# ControlMoteur_ESP32.net
KiCad netlist of a schematic drawn in EasyEDA
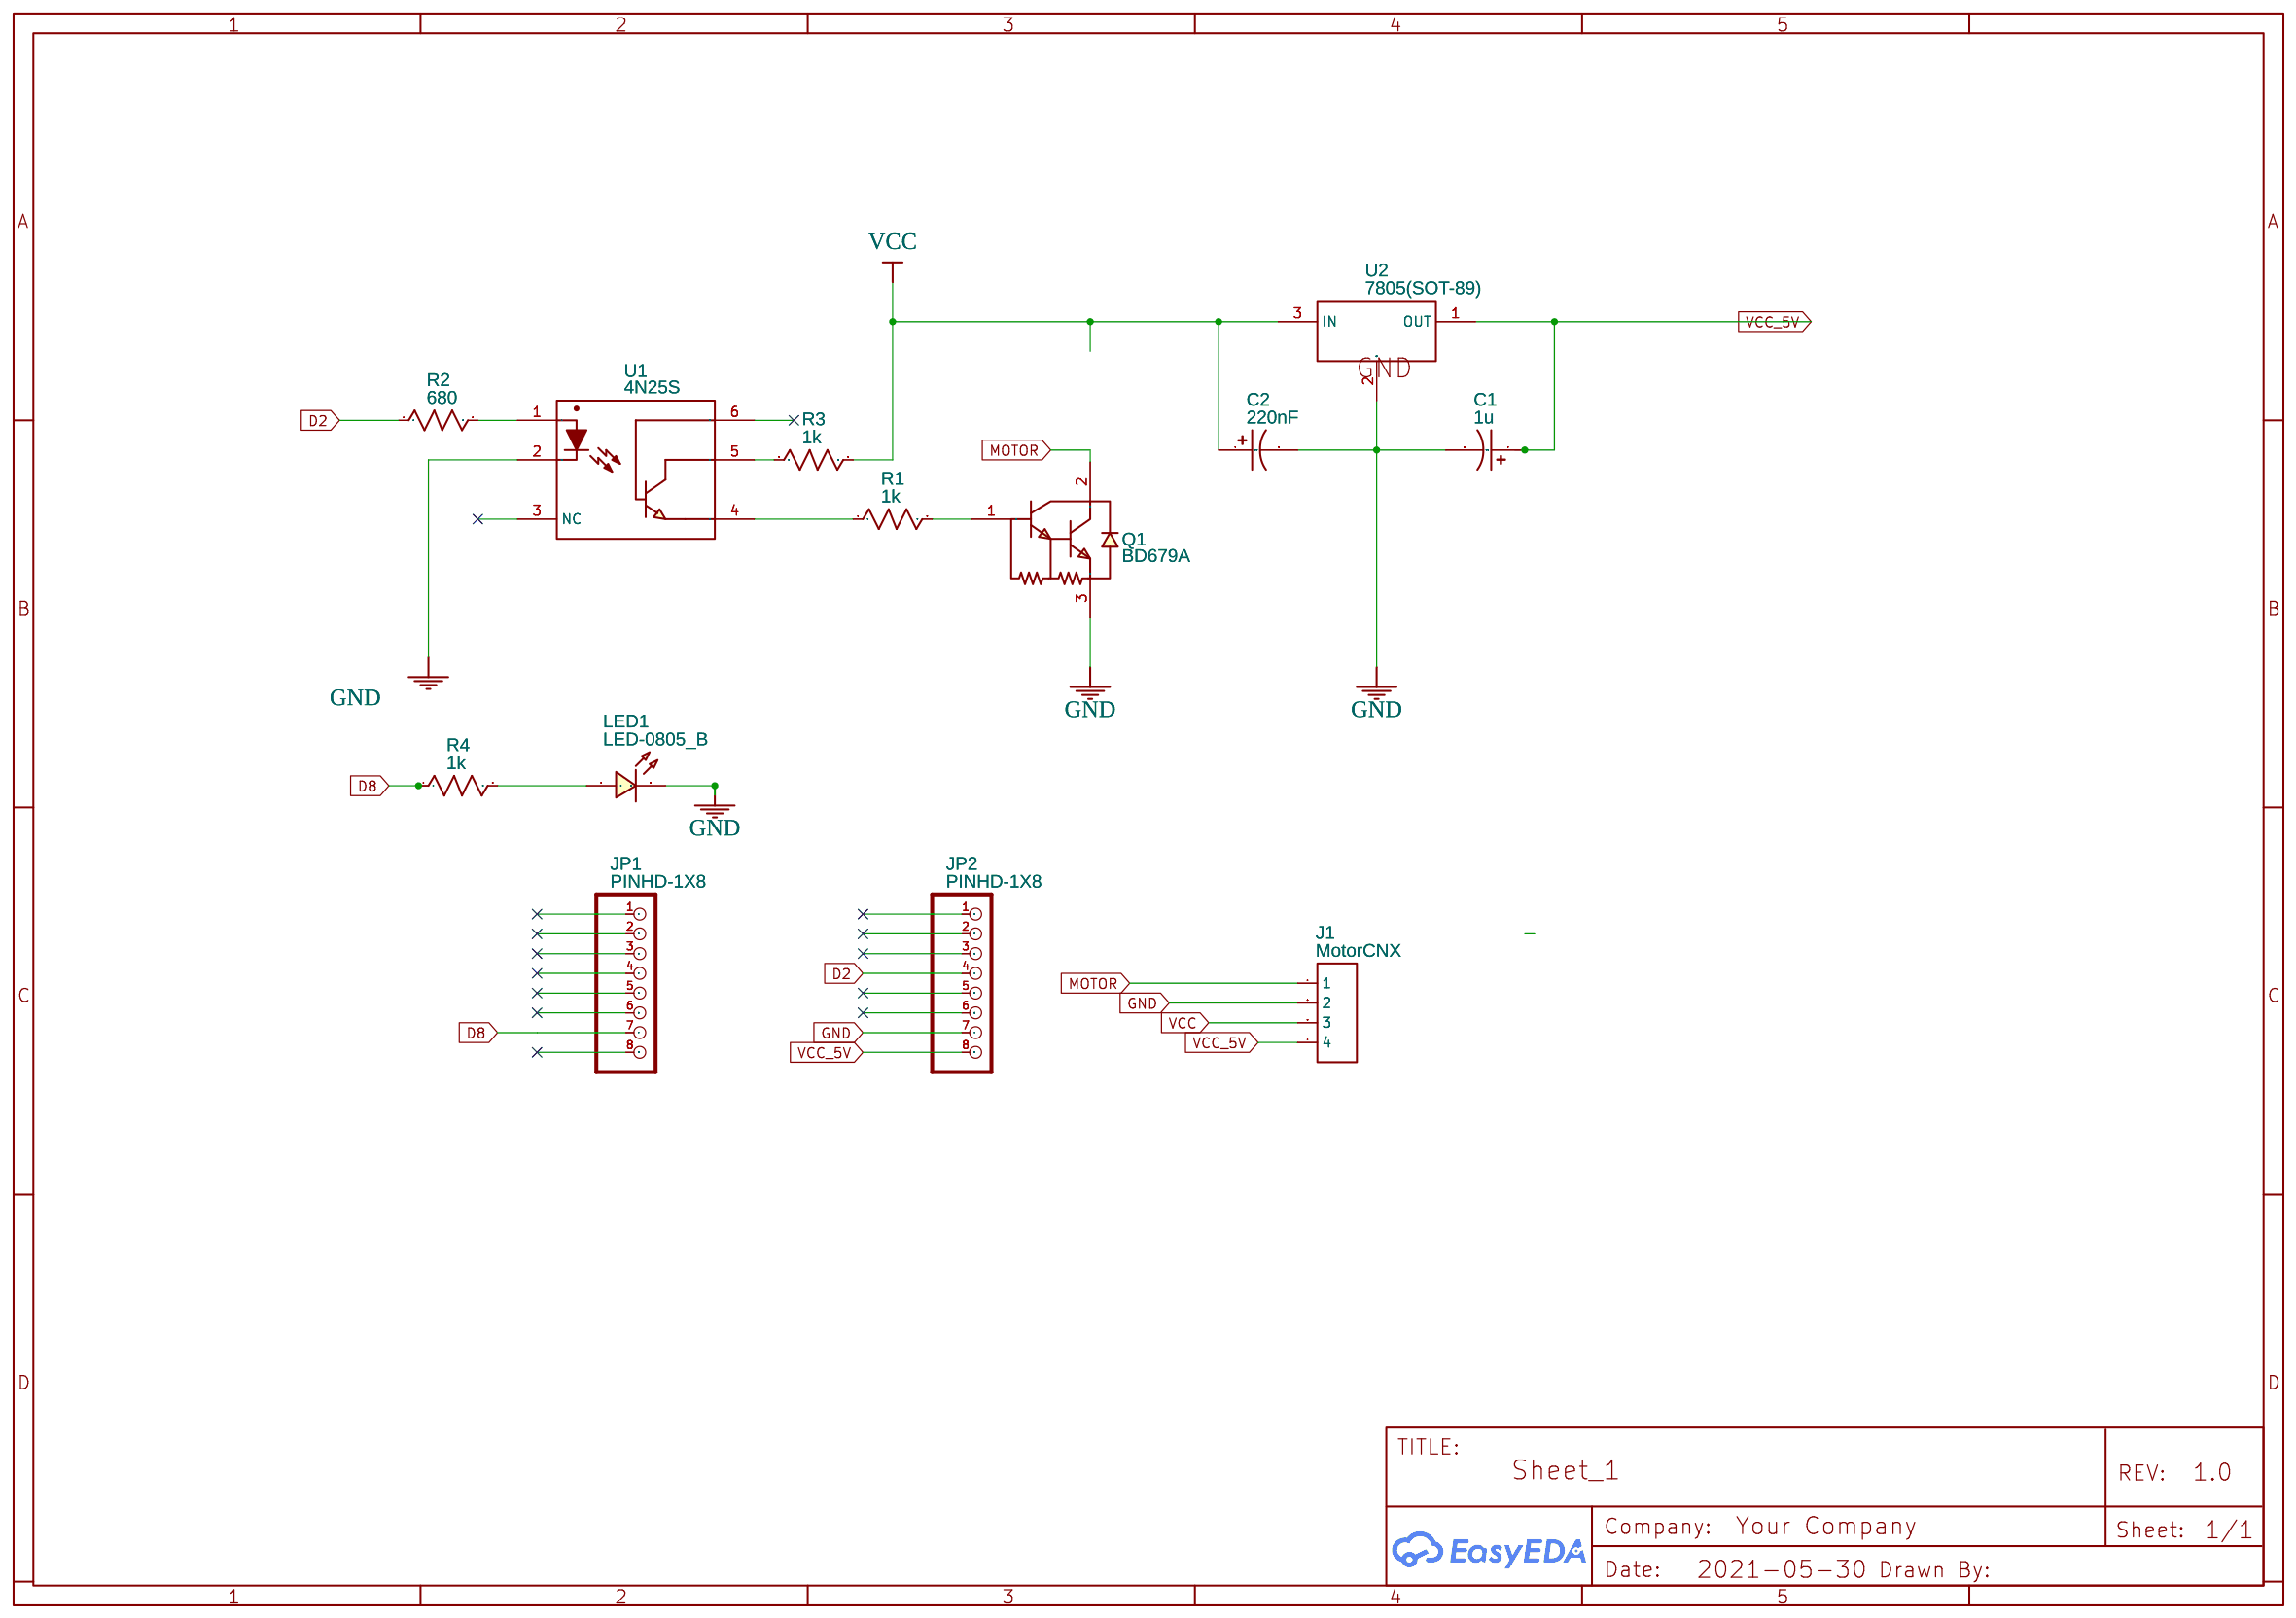
[diagram p0: schematic sheet]

(export (version "E")
  (design (tool "Eeschema 10.0.6"))
  (components
    (comp (ref "C1") (value "1u") (libsource (lib "") (part "C_Tan_SMD_A_US")))
    (comp (ref "C2") (value "220nF") (libsource (lib "") (part "C_Tan_SMD_A_US_1")))
    (comp (ref "J1")
      (value "MotorCNX")
      (fields (field (name "BOM_Supplier Part") "C124378"))
      (libsource (lib "") (part "HDR-M-2.54_1x4"))
    )
    (comp (ref "JP1")
      (value "PINHD-1X8")
      (fields (field (name "BOM_Supplier Part") "C492407"))
      (libsource (lib "") (part "PINHD-1X8"))
    )
    (comp (ref "JP2")
      (value "PINHD-1X8")
      (fields (field (name "BOM_Supplier Part") "C492407"))
      (libsource (lib "") (part "PINHD-1X8"))
    )
    (comp (ref "LED1")
      (value "LED-0805_B")
      (fields
        (field (name "BOM_Manufacturer Part") "D-B080508B1-KS2")
        (field (name "BOM_Supplier Part") "C108412")
      )
      (libsource (lib "") (part "LED-0805_B"))
    )
    (comp (ref "Q1")
      (value "BD679A")
      (fields (field (name "BOM_Supplier Part") "C2760771"))
      (libsource (lib "") (part "BD679A"))
    )
    (comp (ref "R1") (value "1k") (libsource (lib "") (part "R_1210_US")))
    (comp (ref "R2") (value "680") (libsource (lib "") (part "R_1210_US")))
    (comp (ref "R3") (value "1k") (libsource (lib "") (part "R_1210_US")))
    (comp (ref "R4") (value "1k") (libsource (lib "") (part "R_1210_US")))
    (comp (ref "U1")
      (value "4N25S")
      (fields (field (name "BOM_Supplier Part") "C143074"))
      (libsource (lib "") (part "4N25S"))
    )
    (comp (ref "U2")
      (value "7805(SOT-89)")
      (fields (field (name "BOM_Manufacturer Part") "CJ78L05") (field (name "BOM_Supplier Part") "C2079"))
      (libsource (lib "") (part "7805(SOT-89)"))
    )
  )
  (nets
    (net (code "1") (name "D2") (class "Default")
      (node (ref "JP2") (pin "4") (pinfunction "4_4") (pintype "unspecified"))
      (node (ref "R2") (pin "1") (pinfunction "1_1") (pintype "unspecified"))
    )
    (net (code "2") (name "D8") (class "Default")
      (node (ref "JP1") (pin "7") (pinfunction "7_7") (pintype "unspecified"))
      (node (ref "R4") (pin "1") (pinfunction "1_1") (pintype "unspecified"))
    )
    (net (code "3") (name "GND") (class "Default")
      (node (ref "C1") (pin "2") (pinfunction "2_2") (pintype "unspecified"))
      (node (ref "C2") (pin "2") (pinfunction "2_2") (pintype "unspecified"))
      (node (ref "J1") (pin "2") (pinfunction "2_2") (pintype "unspecified"))
      (node (ref "JP2") (pin "7") (pinfunction "7_7") (pintype "unspecified"))
      (node (ref "LED1") (pin "2") (pinfunction "2_2") (pintype "unspecified"))
      (node (ref "Q1") (pin "3") (pinfunction "E_3") (pintype "unspecified"))
      (node (ref "U1") (pin "2") (pinfunction "CAT_2") (pintype "unspecified"))
      (node (ref "U2") (pin "2") (pinfunction "GND_2") (pintype "passive"))
    )
    (net (code "4") (name "MOTOR") (class "Default")
      (node (ref "J1") (pin "1") (pinfunction "1_1") (pintype "unspecified"))
      (node (ref "Q1") (pin "2") (pinfunction "C_2") (pintype "unspecified"))
    )
    (net (code "5") (name "Net-(LED1-Pad1)") (class "Default")
      (node (ref "LED1") (pin "1") (pinfunction "1_1") (pintype "unspecified"))
      (node (ref "R4") (pin "2") (pinfunction "2_2") (pintype "unspecified"))
    )
    (net (code "6") (name "Net-(Q1-B)") (class "Default")
      (node (ref "Q1") (pin "1") (pinfunction "B_1") (pintype "unspecified"))
      (node (ref "R1") (pin "2") (pinfunction "2_2") (pintype "unspecified"))
    )
    (net (code "7") (name "Net-(R1-Pad1)") (class "Default")
      (node (ref "R1") (pin "1") (pinfunction "1_1") (pintype "unspecified"))
      (node (ref "U1") (pin "4") (pinfunction "4_4") (pintype "unspecified"))
    )
    (net (code "8") (name "Net-(R2-Pad2)") (class "Default")
      (node (ref "R2") (pin "2") (pinfunction "2_2") (pintype "unspecified"))
      (node (ref "U1") (pin "1") (pinfunction "1_1") (pintype "unspecified"))
    )
    (net (code "9") (name "Net-(U1-GND)") (class "Default")
      (node (ref "R3") (pin "1") (pinfunction "1_1") (pintype "unspecified"))
      (node (ref "U1") (pin "5") (pinfunction "GND_5") (pintype "unspecified"))
    )
    (net (code "10") (name "VCC") (class "Default")
      (node (ref "C2") (pin "1") (pinfunction "1_1") (pintype "unspecified"))
      (node (ref "J1") (pin "3") (pinfunction "3_3") (pintype "unspecified"))
      (node (ref "R3") (pin "2") (pinfunction "2_2") (pintype "unspecified"))
      (node (ref "U2") (pin "3") (pinfunction "IN_3") (pintype "passive"))
    )
    (net (code "11") (name "VCC_5V") (class "Default")
      (node (ref "C1") (pin "1") (pinfunction "1_1") (pintype "unspecified"))
      (node (ref "J1") (pin "4") (pinfunction "4_4") (pintype "unspecified"))
      (node (ref "JP2") (pin "8") (pinfunction "8_8") (pintype "unspecified"))
      (node (ref "U2") (pin "1") (pinfunction "OUT_1") (pintype "passive"))
    )
    (net (code "12") (name "unconnected-(JP1-Pad1)") (class "Default")
      (node (ref "JP1") (pin "1") (pinfunction "1_1") (pintype "unspecified+no_connect"))
    )
    (net (code "13") (name "unconnected-(JP1-Pad2)") (class "Default")
      (node (ref "JP1") (pin "2") (pinfunction "2_2") (pintype "unspecified+no_connect"))
    )
    (net (code "14") (name "unconnected-(JP1-Pad3)") (class "Default")
      (node (ref "JP1") (pin "3") (pinfunction "3_3") (pintype "unspecified+no_connect"))
    )
    (net (code "15") (name "unconnected-(JP1-Pad4)") (class "Default")
      (node (ref "JP1") (pin "4") (pinfunction "4_4") (pintype "unspecified+no_connect"))
    )
    (net (code "16") (name "unconnected-(JP1-Pad5)") (class "Default")
      (node (ref "JP1") (pin "5") (pinfunction "5_5") (pintype "unspecified+no_connect"))
    )
    (net (code "17") (name "unconnected-(JP1-Pad6)") (class "Default")
      (node (ref "JP1") (pin "6") (pinfunction "6_6") (pintype "unspecified+no_connect"))
    )
    (net (code "18") (name "unconnected-(JP1-Pad8)") (class "Default")
      (node (ref "JP1") (pin "8") (pinfunction "8_8") (pintype "unspecified+no_connect"))
    )
    (net (code "19") (name "unconnected-(JP2-Pad1)") (class "Default")
      (node (ref "JP2") (pin "1") (pinfunction "1_1") (pintype "unspecified+no_connect"))
    )
    (net (code "20") (name "unconnected-(JP2-Pad2)") (class "Default")
      (node (ref "JP2") (pin "2") (pinfunction "2_2") (pintype "unspecified+no_connect"))
    )
    (net (code "21") (name "unconnected-(JP2-Pad3)") (class "Default")
      (node (ref "JP2") (pin "3") (pinfunction "3_3") (pintype "unspecified+no_connect"))
    )
    (net (code "22") (name "unconnected-(JP2-Pad5)") (class "Default")
      (node (ref "JP2") (pin "5") (pinfunction "5_5") (pintype "unspecified+no_connect"))
    )
    (net (code "23") (name "unconnected-(JP2-Pad6)") (class "Default")
      (node (ref "JP2") (pin "6") (pinfunction "6_6") (pintype "unspecified+no_connect"))
    )
    (net (code "24") (name "unconnected-(U1-NC-Pad3)") (class "Default")
      (node (ref "U1") (pin "3") (pinfunction "NC_3") (pintype "unspecified+no_connect"))
    )
    (net (code "25") (name "unconnected-(U1-VO-Pad6)") (class "Default")
      (node (ref "U1") (pin "6") (pinfunction "VO_6") (pintype "unspecified+no_connect"))
    )
  )
)
